# Mechanical.net
KiCad netlist of a schematic drawn in Altium Designer
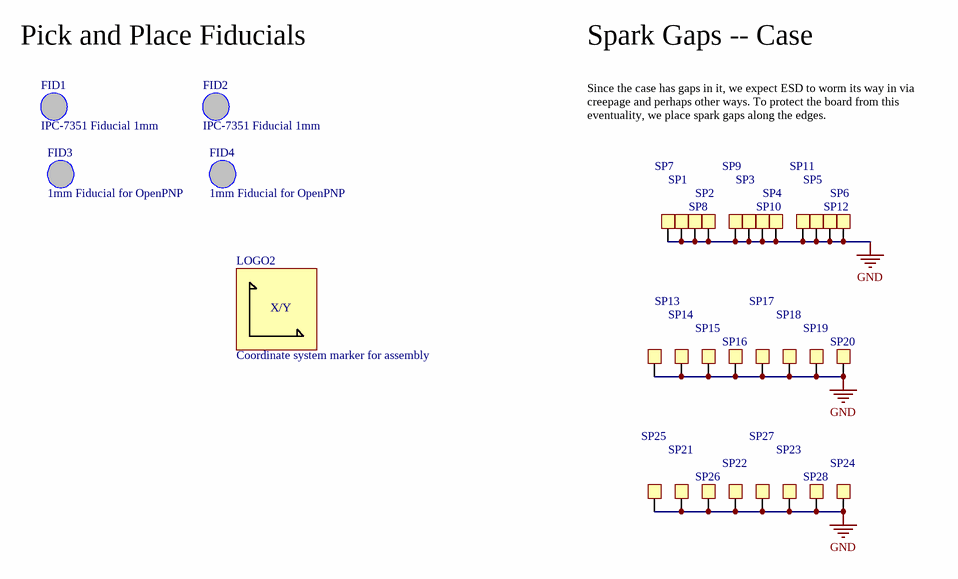
[diagram p0: Mechanical.SchDoc]

(export (version "E")
  (design (tool "Eeschema 10.0.6"))
  (components
    (comp (ref "FID1")
      (value "IPC-7351 Fiducial 1mm")
      (footprint "FIDUCIAL_1.5")
      (libsource (lib "Mechanical") (part "FIDUCIAL_1.5"))
    )
    (comp (ref "FID2")
      (value "IPC-7351 Fiducial 1mm")
      (footprint "FIDUCIAL_1.5")
      (libsource (lib "Mechanical") (part "FIDUCIAL_1.5"))
    )
    (comp (ref "FID3")
      (value "1mm Fiducial for OpenPNP")
      (footprint "FIDUCIAL-NEW")
      (libsource (lib "Mechanical") (part "FIDUCIAL_NEW"))
    )
    (comp (ref "FID4")
      (value "1mm Fiducial for OpenPNP")
      (footprint "FIDUCIAL-NEW")
      (libsource (lib "Mechanical") (part "FIDUCIAL_NEW"))
    )
    (comp (ref "LOGO2")
      (value "Coordinate system marker for assembly")
      (footprint "Coordinate System")
      (libsource (lib "Graphics") (part "CoordinateSystem"))
    )
    (comp (ref "SP1")
      (value "Spark Gap")
      (footprint "SparkGap")
      (description "Open square pad for spark gapping")
      (libsource (lib "PCBFeatures") (part "Spark Gap"))
    )
    (comp (ref "SP2")
      (value "Spark Gap")
      (footprint "SparkGap")
      (description "Open square pad for spark gapping")
      (libsource (lib "PCBFeatures") (part "Spark Gap"))
    )
    (comp (ref "SP3")
      (value "Spark Gap")
      (footprint "SparkGap")
      (description "Open square pad for spark gapping")
      (libsource (lib "PCBFeatures") (part "Spark Gap"))
    )
    (comp (ref "SP4")
      (value "Spark Gap")
      (footprint "SparkGap")
      (description "Open square pad for spark gapping")
      (libsource (lib "PCBFeatures") (part "Spark Gap"))
    )
    (comp (ref "SP5")
      (value "Spark Gap")
      (footprint "SparkGap")
      (description "Open square pad for spark gapping")
      (libsource (lib "PCBFeatures") (part "Spark Gap"))
    )
    (comp (ref "SP6")
      (value "Spark Gap")
      (footprint "SparkGap")
      (description "Open square pad for spark gapping")
      (libsource (lib "PCBFeatures") (part "Spark Gap"))
    )
    (comp (ref "SP7")
      (value "Spark Gap")
      (footprint "SparkGap")
      (description "Open square pad for spark gapping")
      (libsource (lib "PCBFeatures") (part "Spark Gap"))
    )
    (comp (ref "SP8")
      (value "Spark Gap")
      (footprint "SparkGap")
      (description "Open square pad for spark gapping")
      (libsource (lib "PCBFeatures") (part "Spark Gap"))
    )
    (comp (ref "SP9")
      (value "Spark Gap")
      (footprint "SparkGap")
      (description "Open square pad for spark gapping")
      (libsource (lib "PCBFeatures") (part "Spark Gap"))
    )
    (comp (ref "SP10")
      (value "Spark Gap")
      (footprint "SparkGap")
      (description "Open square pad for spark gapping")
      (libsource (lib "PCBFeatures") (part "Spark Gap"))
    )
    (comp (ref "SP11")
      (value "Spark Gap")
      (footprint "SparkGap")
      (description "Open square pad for spark gapping")
      (libsource (lib "PCBFeatures") (part "Spark Gap"))
    )
    (comp (ref "SP12")
      (value "Spark Gap")
      (footprint "SparkGap")
      (description "Open square pad for spark gapping")
      (libsource (lib "PCBFeatures") (part "Spark Gap"))
    )
    (comp (ref "SP13")
      (value "Spark Gap")
      (footprint "SparkGap")
      (description "Open square pad for spark gapping")
      (libsource (lib "PCBFeatures") (part "Spark Gap"))
    )
    (comp (ref "SP14")
      (value "Spark Gap")
      (footprint "SparkGap")
      (description "Open square pad for spark gapping")
      (libsource (lib "PCBFeatures") (part "Spark Gap"))
    )
    (comp (ref "SP15")
      (value "Spark Gap")
      (footprint "SparkGap")
      (description "Open square pad for spark gapping")
      (libsource (lib "PCBFeatures") (part "Spark Gap"))
    )
    (comp (ref "SP16")
      (value "Spark Gap")
      (footprint "SparkGap")
      (description "Open square pad for spark gapping")
      (libsource (lib "PCBFeatures") (part "Spark Gap"))
    )
    (comp (ref "SP17")
      (value "Spark Gap")
      (footprint "SparkGap")
      (description "Open square pad for spark gapping")
      (libsource (lib "PCBFeatures") (part "Spark Gap"))
    )
    (comp (ref "SP18")
      (value "Spark Gap")
      (footprint "SparkGap")
      (description "Open square pad for spark gapping")
      (libsource (lib "PCBFeatures") (part "Spark Gap"))
    )
    (comp (ref "SP19")
      (value "Spark Gap")
      (footprint "SparkGap")
      (description "Open square pad for spark gapping")
      (libsource (lib "PCBFeatures") (part "Spark Gap"))
    )
    (comp (ref "SP20")
      (value "Spark Gap")
      (footprint "SparkGap")
      (description "Open square pad for spark gapping")
      (libsource (lib "PCBFeatures") (part "Spark Gap"))
    )
    (comp (ref "SP21")
      (value "Spark Gap")
      (footprint "SparkGap")
      (description "Open square pad for spark gapping")
      (libsource (lib "PCBFeatures") (part "Spark Gap"))
    )
    (comp (ref "SP22")
      (value "Spark Gap")
      (footprint "SparkGap")
      (description "Open square pad for spark gapping")
      (libsource (lib "PCBFeatures") (part "Spark Gap"))
    )
    (comp (ref "SP23")
      (value "Spark Gap")
      (footprint "SparkGap")
      (description "Open square pad for spark gapping")
      (libsource (lib "PCBFeatures") (part "Spark Gap"))
    )
    (comp (ref "SP24")
      (value "Spark Gap")
      (footprint "SparkGap")
      (description "Open square pad for spark gapping")
      (libsource (lib "PCBFeatures") (part "Spark Gap"))
    )
    (comp (ref "SP25")
      (value "Spark Gap")
      (footprint "SparkGap")
      (description "Open square pad for spark gapping")
      (libsource (lib "PCBFeatures") (part "Spark Gap"))
    )
    (comp (ref "SP26")
      (value "Spark Gap")
      (footprint "SparkGap")
      (description "Open square pad for spark gapping")
      (libsource (lib "PCBFeatures") (part "Spark Gap"))
    )
    (comp (ref "SP27")
      (value "Spark Gap")
      (footprint "SparkGap")
      (description "Open square pad for spark gapping")
      (libsource (lib "PCBFeatures") (part "Spark Gap"))
    )
    (comp (ref "SP28")
      (value "Spark Gap")
      (footprint "SparkGap")
      (description "Open square pad for spark gapping")
      (libsource (lib "PCBFeatures") (part "Spark Gap"))
    )
  )
  (nets
    (net (code "1") (name "GND") (class "Default")
      (node (ref "SP1") (pin "1") (pinfunction "1_1") (pintype "passive"))
      (node (ref "SP10") (pin "1") (pinfunction "1_1") (pintype "passive"))
      (node (ref "SP11") (pin "1") (pinfunction "1_1") (pintype "passive"))
      (node (ref "SP12") (pin "1") (pinfunction "1_1") (pintype "passive"))
      (node (ref "SP13") (pin "1") (pinfunction "1_1") (pintype "passive"))
      (node (ref "SP14") (pin "1") (pinfunction "1_1") (pintype "passive"))
      (node (ref "SP15") (pin "1") (pinfunction "1_1") (pintype "passive"))
      (node (ref "SP16") (pin "1") (pinfunction "1_1") (pintype "passive"))
      (node (ref "SP17") (pin "1") (pinfunction "1_1") (pintype "passive"))
      (node (ref "SP18") (pin "1") (pinfunction "1_1") (pintype "passive"))
      (node (ref "SP19") (pin "1") (pinfunction "1_1") (pintype "passive"))
      (node (ref "SP2") (pin "1") (pinfunction "1_1") (pintype "passive"))
      (node (ref "SP20") (pin "1") (pinfunction "1_1") (pintype "passive"))
      (node (ref "SP21") (pin "1") (pinfunction "1_1") (pintype "passive"))
      (node (ref "SP22") (pin "1") (pinfunction "1_1") (pintype "passive"))
      (node (ref "SP23") (pin "1") (pinfunction "1_1") (pintype "passive"))
      (node (ref "SP24") (pin "1") (pinfunction "1_1") (pintype "passive"))
      (node (ref "SP25") (pin "1") (pinfunction "1_1") (pintype "passive"))
      (node (ref "SP26") (pin "1") (pinfunction "1_1") (pintype "passive"))
      (node (ref "SP27") (pin "1") (pinfunction "1_1") (pintype "passive"))
      (node (ref "SP28") (pin "1") (pinfunction "1_1") (pintype "passive"))
      (node (ref "SP3") (pin "1") (pinfunction "1_1") (pintype "passive"))
      (node (ref "SP4") (pin "1") (pinfunction "1_1") (pintype "passive"))
      (node (ref "SP5") (pin "1") (pinfunction "1_1") (pintype "passive"))
      (node (ref "SP6") (pin "1") (pinfunction "1_1") (pintype "passive"))
      (node (ref "SP7") (pin "1") (pinfunction "1_1") (pintype "passive"))
      (node (ref "SP8") (pin "1") (pinfunction "1_1") (pintype "passive"))
      (node (ref "SP9") (pin "1") (pinfunction "1_1") (pintype "passive"))
    )
    (net (code "2") (name "unconnected-(FID1-Pad1)") (class "Default")
      (node (ref "FID1") (pin "1") (pinfunction "1_1") (pintype "passive"))
    )
    (net (code "3") (name "unconnected-(FID2-Pad1)") (class "Default")
      (node (ref "FID2") (pin "1") (pinfunction "1_1") (pintype "passive"))
    )
    (net (code "4") (name "unconnected-(FID3-Pad1)") (class "Default")
      (node (ref "FID3") (pin "1") (pinfunction "1_1") (pintype "passive"))
    )
    (net (code "5") (name "unconnected-(FID4-Pad1)") (class "Default")
      (node (ref "FID4") (pin "1") (pinfunction "1_1") (pintype "passive"))
    )
  )
)
